# MotionGlove.net
KiCad netlist of a schematic drawn in Altium Designer
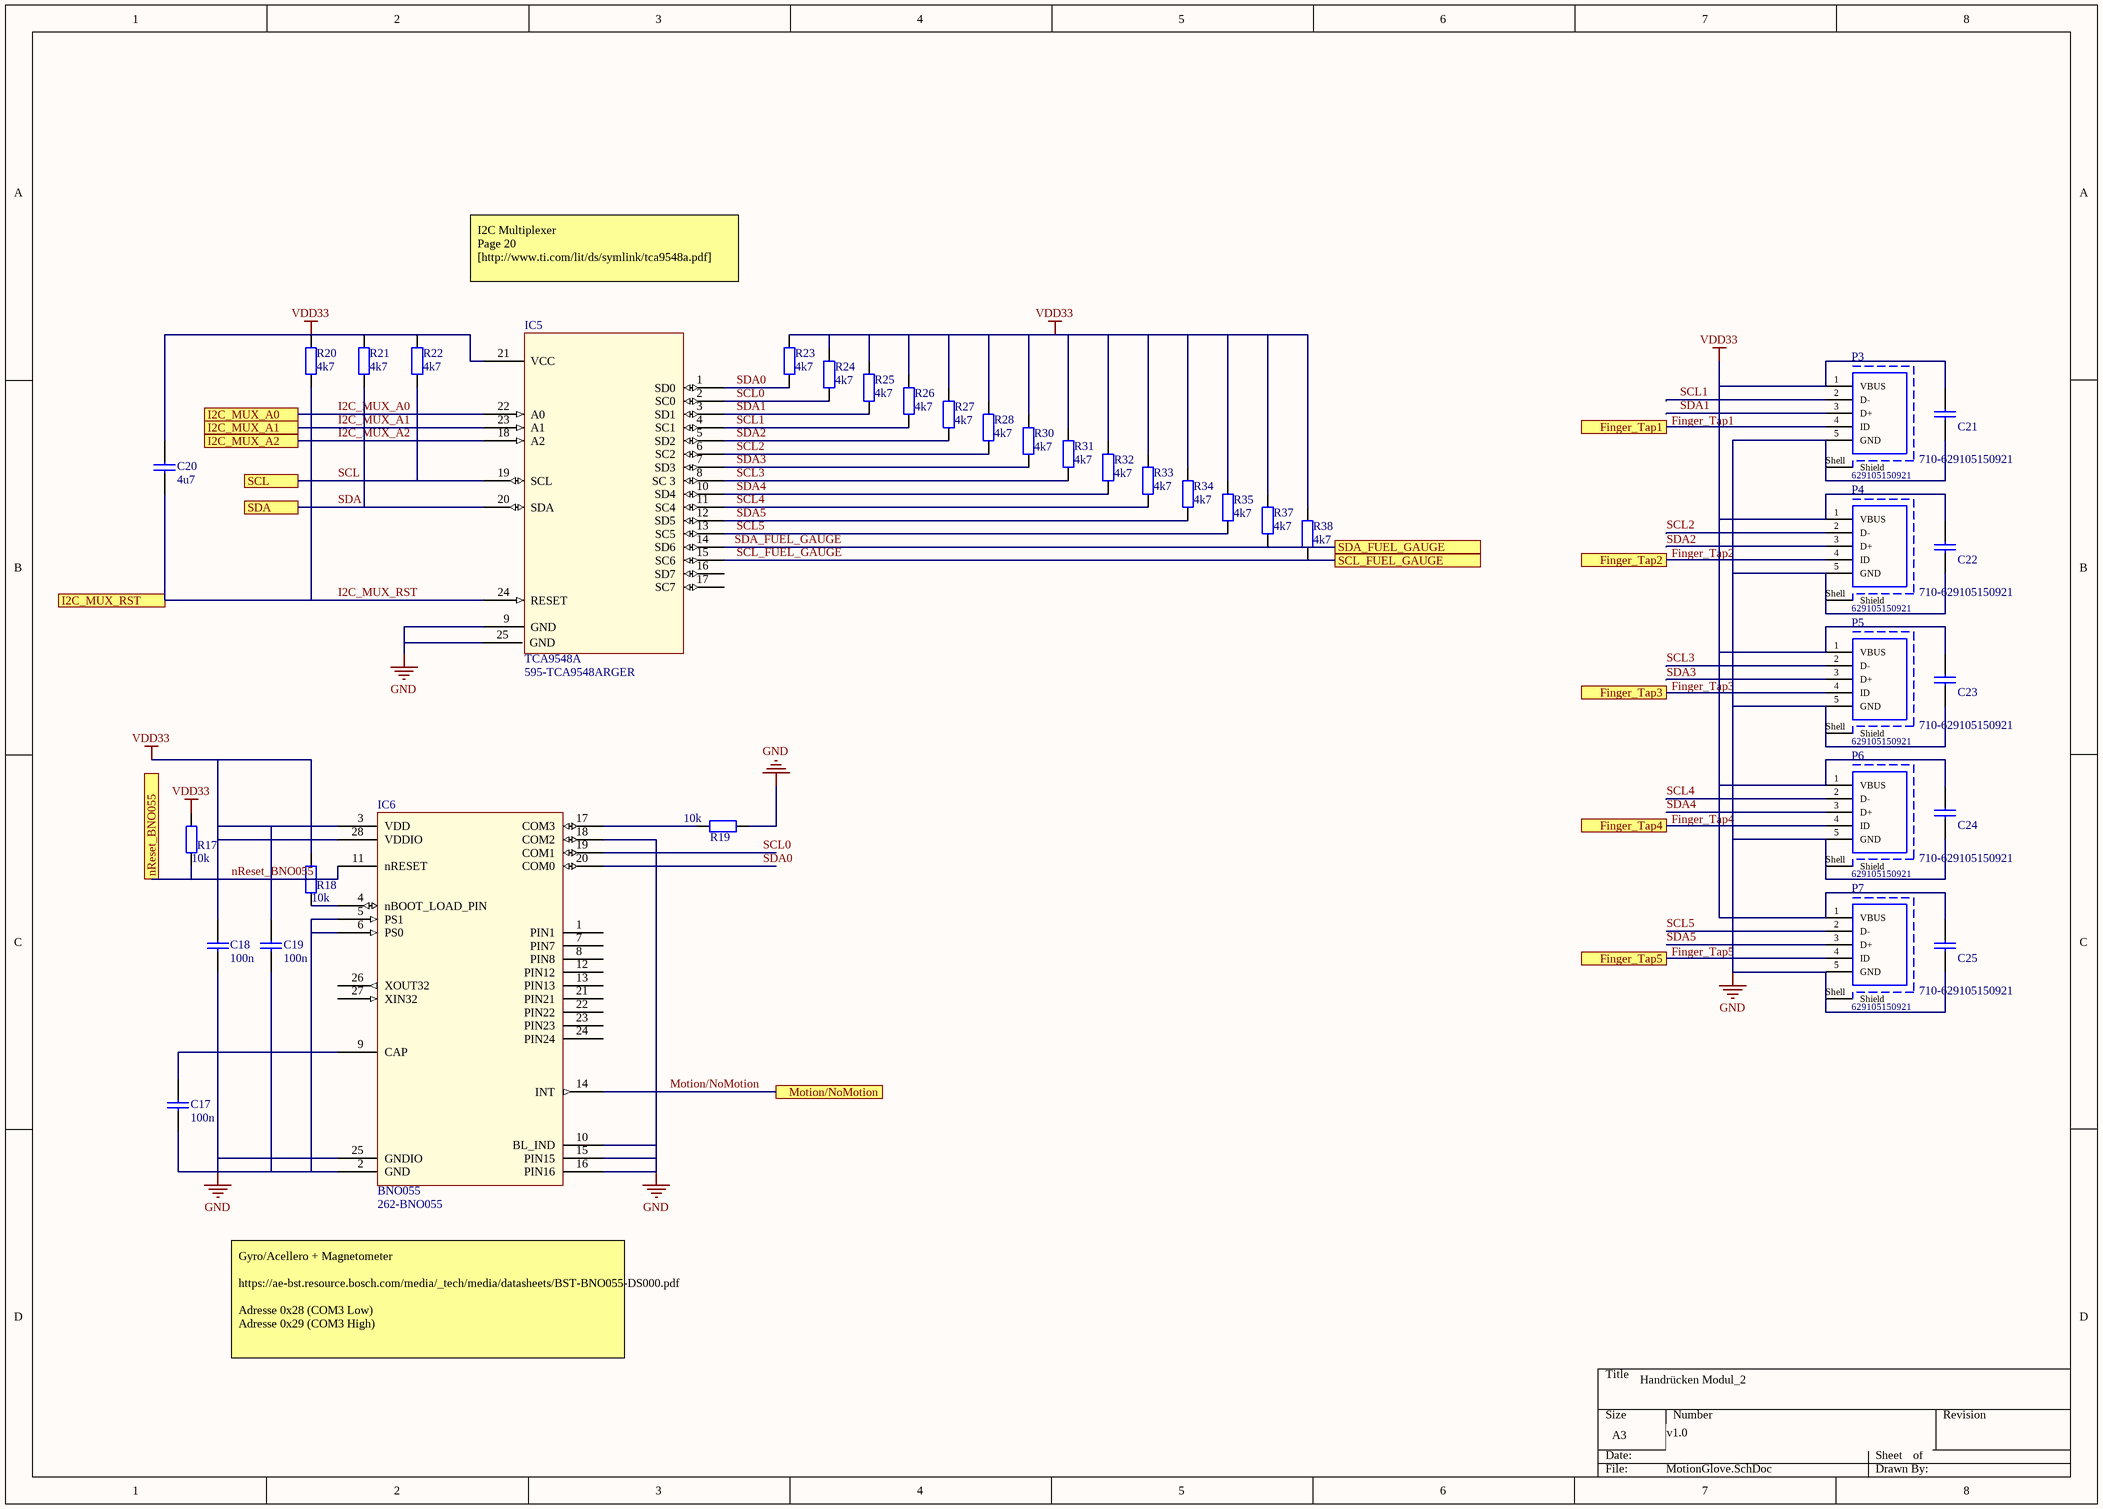
[diagram p0: MotionGlove.SchDoc]

(export (version "E")
  (design (tool "Eeschema 10.0.6"))
  (components
    (comp (ref "C17")
      (value "100n")
      (footprint "CAPC1005X55")
      (description "Ceramic Chip Capacitor")
      (fields (field (name "MANUFACTURER") "Kemet") (field (name "VOLTAGE") "16V"))
      (libsource (lib "SCT_MySQL_5.1") (part "Capacitor"))
    )
    (comp (ref "C18")
      (value "100n")
      (footprint "CAPC1005X55")
      (description "Ceramic Chip Capacitor")
      (fields (field (name "MANUFACTURER") "Kemet") (field (name "VOLTAGE") "16V"))
      (libsource (lib "SCT_MySQL_5.1") (part "Capacitor"))
    )
    (comp (ref "C19")
      (value "100n")
      (footprint "CAPC1005X55")
      (description "Ceramic Chip Capacitor")
      (fields (field (name "MANUFACTURER") "Kemet") (field (name "VOLTAGE") "16V"))
      (libsource (lib "SCT_MySQL_5.1") (part "Capacitor"))
    )
    (comp (ref "C20")
      (value "4u7")
      (footprint "CAPC1005X55")
      (description "Ceramic Chip Capacitor")
      (fields (field (name "MANUFACTURER") "Murata") (field (name "VOLTAGE") "6.3V"))
      (libsource (lib "SCT_MySQL_5.1") (part "Capacitor"))
    )
    (comp (ref "C21")
      (value "100n")
      (footprint "CAPC1005X55")
      (description "Ceramic Chip Capacitor")
      (fields (field (name "MANUFACTURER") "Kemet") (field (name "VOLTAGE") "16V"))
      (libsource (lib "SCT_MySQL_5.1") (part "Capacitor"))
    )
    (comp (ref "C22")
      (value "100n")
      (footprint "CAPC1005X55")
      (description "Ceramic Chip Capacitor")
      (fields (field (name "MANUFACTURER") "Kemet") (field (name "VOLTAGE") "16V"))
      (libsource (lib "SCT_MySQL_5.1") (part "Capacitor"))
    )
    (comp (ref "C23")
      (value "100n")
      (footprint "CAPC1005X55")
      (description "Ceramic Chip Capacitor")
      (fields (field (name "MANUFACTURER") "Kemet") (field (name "VOLTAGE") "16V"))
      (libsource (lib "SCT_MySQL_5.1") (part "Capacitor"))
    )
    (comp (ref "C24")
      (value "100n")
      (footprint "CAPC1005X55")
      (description "Ceramic Chip Capacitor")
      (fields (field (name "MANUFACTURER") "Kemet") (field (name "VOLTAGE") "16V"))
      (libsource (lib "SCT_MySQL_5.1") (part "Capacitor"))
    )
    (comp (ref "C25")
      (value "100n")
      (footprint "CAPC1005X55")
      (description "Ceramic Chip Capacitor")
      (fields (field (name "MANUFACTURER") "Kemet") (field (name "VOLTAGE") "16V"))
      (libsource (lib "SCT_MySQL_5.1") (part "Capacitor"))
    )
    (comp (ref "IC5")
      (value "TCA9548A")
      (footprint "TCA9548A-Q1")
      (fields (field (name "SUPPLIER PART NUMBER 1") "595-TCA9548ARGER"))
      (libsource (lib "Lib") (part "TCA9548A"))
    )
    (comp (ref "IC6")
      (value "BNO055")
      (footprint "BNO055")
      (fields (field (name "SUPPLIER PART NUMBER 1") "262-BNO055"))
      (libsource (lib "Lib") (part "BNO055"))
    )
    (comp (ref "P3")
      (value "629105150921")
      (footprint "629105150921")
      (description "Micro USB 2.0 Type AB Receptacle WR-COM, Horizontal, SMT")
      (fields
        (field (name "SUPPLIER PART NUMBER 1") "710-629105150921")
        (field (name "PUBLISHER") "Wurth Elektronik")
      )
      (libsource (lib "USB Connectors WR-USB") (part "629105150921"))
    )
    (comp (ref "P4")
      (value "629105150921")
      (footprint "629105150921")
      (description "Micro USB 2.0 Type AB Receptacle WR-COM, Horizontal, SMT")
      (fields
        (field (name "SUPPLIER PART NUMBER 1") "710-629105150921")
        (field (name "PUBLISHER") "Wurth Elektronik")
      )
      (libsource (lib "USB Connectors WR-USB") (part "629105150921"))
    )
    (comp (ref "P5")
      (value "629105150921")
      (footprint "629105150921")
      (description "Micro USB 2.0 Type AB Receptacle WR-COM, Horizontal, SMT")
      (fields
        (field (name "SUPPLIER PART NUMBER 1") "710-629105150921")
        (field (name "PUBLISHER") "Wurth Elektronik")
      )
      (libsource (lib "USB Connectors WR-USB") (part "629105150921"))
    )
    (comp (ref "P6")
      (value "629105150921")
      (footprint "629105150921")
      (description "Micro USB 2.0 Type AB Receptacle WR-COM, Horizontal, SMT")
      (fields
        (field (name "SUPPLIER PART NUMBER 1") "710-629105150921")
        (field (name "PUBLISHER") "Wurth Elektronik")
      )
      (libsource (lib "USB Connectors WR-USB") (part "629105150921"))
    )
    (comp (ref "P7")
      (value "629105150921")
      (footprint "629105150921")
      (description "Micro USB 2.0 Type AB Receptacle WR-COM, Horizontal, SMT")
      (fields
        (field (name "SUPPLIER PART NUMBER 1") "710-629105150921")
        (field (name "PUBLISHER") "Wurth Elektronik")
      )
      (libsource (lib "USB Connectors WR-USB") (part "629105150921"))
    )
    (comp (ref "R17")
      (value "10k")
      (footprint "RESC1005X40")
      (description "Resistor")
      (fields (field (name "MANUFACTURER") "Multicomp") (field (name "TOLERANCE") "±1%"))
      (libsource (lib "SCT_MySQL_5.1") (part "Resistor"))
    )
    (comp (ref "R18")
      (value "10k")
      (footprint "RESC1005X40")
      (description "Resistor")
      (fields (field (name "MANUFACTURER") "Multicomp") (field (name "TOLERANCE") "±1%"))
      (libsource (lib "SCT_MySQL_5.1") (part "Resistor"))
    )
    (comp (ref "R19")
      (value "10k")
      (footprint "RESC1005X40")
      (description "Resistor")
      (fields (field (name "MANUFACTURER") "Multicomp") (field (name "TOLERANCE") "±1%"))
      (libsource (lib "") (part "Resistor_1"))
    )
    (comp (ref "R20")
      (value "4k7")
      (footprint "RESC1005X40")
      (description "Resistor")
      (fields (field (name "MANUFACTURER") "Multicomp") (field (name "TOLERANCE") "±1%"))
      (libsource (lib "SCT_MySQL_5.1") (part "Resistor"))
    )
    (comp (ref "R21")
      (value "4k7")
      (footprint "RESC1005X40")
      (description "Resistor")
      (fields (field (name "MANUFACTURER") "Multicomp") (field (name "TOLERANCE") "±1%"))
      (libsource (lib "SCT_MySQL_5.1") (part "Resistor"))
    )
    (comp (ref "R22")
      (value "4k7")
      (footprint "RESC1005X40")
      (description "Resistor")
      (fields (field (name "MANUFACTURER") "Multicomp") (field (name "TOLERANCE") "±1%"))
      (libsource (lib "SCT_MySQL_5.1") (part "Resistor"))
    )
    (comp (ref "R23")
      (value "4k7")
      (footprint "RESC1005X40")
      (description "Resistor")
      (fields (field (name "MANUFACTURER") "Multicomp") (field (name "TOLERANCE") "±1%"))
      (libsource (lib "SCT_MySQL_5.1") (part "Resistor"))
    )
    (comp (ref "R24")
      (value "4k7")
      (footprint "RESC1005X40")
      (description "Resistor")
      (fields (field (name "MANUFACTURER") "Multicomp") (field (name "TOLERANCE") "±1%"))
      (libsource (lib "SCT_MySQL_5.1") (part "Resistor"))
    )
    (comp (ref "R25")
      (value "4k7")
      (footprint "RESC1005X40")
      (description "Resistor")
      (fields (field (name "MANUFACTURER") "Multicomp") (field (name "TOLERANCE") "±1%"))
      (libsource (lib "SCT_MySQL_5.1") (part "Resistor"))
    )
    (comp (ref "R26")
      (value "4k7")
      (footprint "RESC1005X40")
      (description "Resistor")
      (fields (field (name "MANUFACTURER") "Multicomp") (field (name "TOLERANCE") "±1%"))
      (libsource (lib "SCT_MySQL_5.1") (part "Resistor"))
    )
    (comp (ref "R27")
      (value "4k7")
      (footprint "RESC1005X40")
      (description "Resistor")
      (fields (field (name "MANUFACTURER") "Multicomp") (field (name "TOLERANCE") "±1%"))
      (libsource (lib "SCT_MySQL_5.1") (part "Resistor"))
    )
    (comp (ref "R28")
      (value "4k7")
      (footprint "RESC1005X40")
      (description "Resistor")
      (fields (field (name "MANUFACTURER") "Multicomp") (field (name "TOLERANCE") "±1%"))
      (libsource (lib "SCT_MySQL_5.1") (part "Resistor"))
    )
    (comp (ref "R30")
      (value "4k7")
      (footprint "RESC1005X40")
      (description "Resistor")
      (fields (field (name "MANUFACTURER") "Multicomp") (field (name "TOLERANCE") "±1%"))
      (libsource (lib "SCT_MySQL_5.1") (part "Resistor"))
    )
    (comp (ref "R31")
      (value "4k7")
      (footprint "RESC1005X40")
      (description "Resistor")
      (fields (field (name "MANUFACTURER") "Multicomp") (field (name "TOLERANCE") "±1%"))
      (libsource (lib "SCT_MySQL_5.1") (part "Resistor"))
    )
    (comp (ref "R32")
      (value "4k7")
      (footprint "RESC1005X40")
      (description "Resistor")
      (fields (field (name "MANUFACTURER") "Multicomp") (field (name "TOLERANCE") "±1%"))
      (libsource (lib "SCT_MySQL_5.1") (part "Resistor"))
    )
    (comp (ref "R33")
      (value "4k7")
      (footprint "RESC1005X40")
      (description "Resistor")
      (fields (field (name "MANUFACTURER") "Multicomp") (field (name "TOLERANCE") "±1%"))
      (libsource (lib "SCT_MySQL_5.1") (part "Resistor"))
    )
    (comp (ref "R34")
      (value "4k7")
      (footprint "RESC1005X40")
      (description "Resistor")
      (fields (field (name "MANUFACTURER") "Multicomp") (field (name "TOLERANCE") "±1%"))
      (libsource (lib "SCT_MySQL_5.1") (part "Resistor"))
    )
    (comp (ref "R35")
      (value "4k7")
      (footprint "RESC1005X40")
      (description "Resistor")
      (fields (field (name "MANUFACTURER") "Multicomp") (field (name "TOLERANCE") "±1%"))
      (libsource (lib "SCT_MySQL_5.1") (part "Resistor"))
    )
    (comp (ref "R37")
      (value "4k7")
      (footprint "RESC1005X40")
      (description "Resistor")
      (fields (field (name "MANUFACTURER") "Multicomp") (field (name "TOLERANCE") "±1%"))
      (libsource (lib "SCT_MySQL_5.1") (part "Resistor"))
    )
    (comp (ref "R38")
      (value "4k7")
      (footprint "RESC1005X40")
      (description "Resistor")
      (fields (field (name "MANUFACTURER") "Multicomp") (field (name "TOLERANCE") "±1%"))
      (libsource (lib "SCT_MySQL_5.1") (part "Resistor"))
    )
  )
  (nets
    (net (code "1") (name "/Finger_Tap1") (class "Default")
      (node (ref "P3") (pin "4") (pinfunction "ID_4") (pintype "passive"))
    )
    (net (code "2") (name "/Finger_Tap2") (class "Default")
      (node (ref "P4") (pin "4") (pinfunction "ID_4") (pintype "passive"))
    )
    (net (code "3") (name "/Finger_Tap3") (class "Default")
      (node (ref "P5") (pin "4") (pinfunction "ID_4") (pintype "passive"))
    )
    (net (code "4") (name "/Finger_Tap4") (class "Default")
      (node (ref "P6") (pin "4") (pinfunction "ID_4") (pintype "passive"))
    )
    (net (code "5") (name "/Finger_Tap5") (class "Default")
      (node (ref "P7") (pin "4") (pinfunction "ID_4") (pintype "passive"))
    )
    (net (code "6") (name "/I2C_MUX_A0") (class "Default")
      (node (ref "IC5") (pin "22") (pinfunction "A0_22") (pintype "input"))
    )
    (net (code "7") (name "/I2C_MUX_A1") (class "Default")
      (node (ref "IC5") (pin "23") (pinfunction "A1_23") (pintype "input"))
    )
    (net (code "8") (name "/I2C_MUX_A2") (class "Default")
      (node (ref "IC5") (pin "18") (pinfunction "A2_18") (pintype "input"))
    )
    (net (code "9") (name "/I2C_MUX_RST") (class "Default")
      (node (ref "C20") (pin "1") (pinfunction "1_1") (pintype "passive"))
      (node (ref "IC5") (pin "24") (pinfunction "RESET_24") (pintype "input"))
      (node (ref "R20") (pin "1") (pinfunction "1_1") (pintype "passive"))
    )
    (net (code "10") (name "/Motion{slash}NoMotion") (class "Default")
      (node (ref "IC6") (pin "14") (pinfunction "INT_14") (pintype "output"))
    )
    (net (code "11") (name "/SCL") (class "Default")
      (node (ref "IC5") (pin "19") (pinfunction "SCL_19") (pintype "bidirectional"))
      (node (ref "R22") (pin "1") (pinfunction "1_1") (pintype "passive"))
    )
    (net (code "12") (name "/SCL0") (class "Default")
      (node (ref "IC5") (pin "2") (pinfunction "SC0_2") (pintype "bidirectional"))
      (node (ref "IC6") (pin "19") (pinfunction "COM1_19") (pintype "bidirectional"))
      (node (ref "R24") (pin "1") (pinfunction "1_1") (pintype "passive"))
    )
    (net (code "13") (name "/SCL1") (class "Default")
      (node (ref "IC5") (pin "4") (pinfunction "SC1_4") (pintype "bidirectional"))
      (node (ref "P3") (pin "2") (pinfunction "D-_2") (pintype "passive"))
      (node (ref "R26") (pin "1") (pinfunction "1_1") (pintype "passive"))
    )
    (net (code "14") (name "/SCL2") (class "Default")
      (node (ref "IC5") (pin "6") (pinfunction "SC2_6") (pintype "bidirectional"))
      (node (ref "P4") (pin "2") (pinfunction "D-_2") (pintype "passive"))
      (node (ref "R28") (pin "1") (pinfunction "1_1") (pintype "passive"))
    )
    (net (code "15") (name "/SCL3") (class "Default")
      (node (ref "IC5") (pin "8") (pinfunction "SC_3_8") (pintype "bidirectional"))
      (node (ref "P5") (pin "2") (pinfunction "D-_2") (pintype "passive"))
      (node (ref "R31") (pin "1") (pinfunction "1_1") (pintype "passive"))
    )
    (net (code "16") (name "/SCL4") (class "Default")
      (node (ref "IC5") (pin "11") (pinfunction "SC4_11") (pintype "bidirectional"))
      (node (ref "P6") (pin "2") (pinfunction "D-_2") (pintype "passive"))
      (node (ref "R33") (pin "1") (pinfunction "1_1") (pintype "passive"))
    )
    (net (code "17") (name "/SCL5") (class "Default")
      (node (ref "IC5") (pin "13") (pinfunction "SC5_13") (pintype "bidirectional"))
      (node (ref "P7") (pin "2") (pinfunction "D-_2") (pintype "passive"))
      (node (ref "R35") (pin "1") (pinfunction "1_1") (pintype "passive"))
    )
    (net (code "18") (name "/SCL_FUEL_GAUGE") (class "Default")
      (node (ref "IC5") (pin "15") (pinfunction "SC6_15") (pintype "bidirectional"))
      (node (ref "R38") (pin "1") (pinfunction "1_1") (pintype "passive"))
    )
    (net (code "19") (name "/SDA") (class "Default")
      (node (ref "IC5") (pin "20") (pinfunction "SDA_20") (pintype "bidirectional"))
      (node (ref "R21") (pin "1") (pinfunction "1_1") (pintype "passive"))
    )
    (net (code "20") (name "/SDA0") (class "Default")
      (node (ref "IC5") (pin "1") (pinfunction "SD0_1") (pintype "bidirectional"))
      (node (ref "IC6") (pin "20") (pinfunction "COM0_20") (pintype "bidirectional"))
      (node (ref "R23") (pin "1") (pinfunction "1_1") (pintype "passive"))
    )
    (net (code "21") (name "/SDA1") (class "Default")
      (node (ref "IC5") (pin "3") (pinfunction "SD1_3") (pintype "bidirectional"))
      (node (ref "P3") (pin "3") (pinfunction "D+_3") (pintype "passive"))
      (node (ref "R25") (pin "1") (pinfunction "1_1") (pintype "passive"))
    )
    (net (code "22") (name "/SDA2") (class "Default")
      (node (ref "IC5") (pin "5") (pinfunction "SD2_5") (pintype "bidirectional"))
      (node (ref "P4") (pin "3") (pinfunction "D+_3") (pintype "passive"))
      (node (ref "R27") (pin "1") (pinfunction "1_1") (pintype "passive"))
    )
    (net (code "23") (name "/SDA3") (class "Default")
      (node (ref "IC5") (pin "7") (pinfunction "SD3_7") (pintype "bidirectional"))
      (node (ref "P5") (pin "3") (pinfunction "D+_3") (pintype "passive"))
      (node (ref "R30") (pin "1") (pinfunction "1_1") (pintype "passive"))
    )
    (net (code "24") (name "/SDA4") (class "Default")
      (node (ref "IC5") (pin "10") (pinfunction "SD4_10") (pintype "bidirectional"))
      (node (ref "P6") (pin "3") (pinfunction "D+_3") (pintype "passive"))
      (node (ref "R32") (pin "1") (pinfunction "1_1") (pintype "passive"))
    )
    (net (code "25") (name "/SDA5") (class "Default")
      (node (ref "IC5") (pin "12") (pinfunction "SD5_12") (pintype "bidirectional"))
      (node (ref "P7") (pin "3") (pinfunction "D+_3") (pintype "passive"))
      (node (ref "R34") (pin "1") (pinfunction "1_1") (pintype "passive"))
    )
    (net (code "26") (name "/SDA_FUEL_GAUGE") (class "Default")
      (node (ref "IC5") (pin "14") (pinfunction "SD6_14") (pintype "bidirectional"))
      (node (ref "R37") (pin "1") (pinfunction "1_1") (pintype "passive"))
    )
    (net (code "27") (name "/nReset_BNO055") (class "Default")
      (node (ref "IC6") (pin "11") (pinfunction "nRESET_11") (pintype "passive"))
      (node (ref "R17") (pin "1") (pinfunction "1_1") (pintype "passive"))
    )
    (net (code "28") (name "GND") (class "Default")
      (node (ref "C17") (pin "1") (pinfunction "1_1") (pintype "passive"))
      (node (ref "C18") (pin "1") (pinfunction "1_1") (pintype "passive"))
      (node (ref "C19") (pin "1") (pinfunction "1_1") (pintype "passive"))
      (node (ref "C21") (pin "1") (pinfunction "1_1") (pintype "passive"))
      (node (ref "C22") (pin "1") (pinfunction "1_1") (pintype "passive"))
      (node (ref "C23") (pin "1") (pinfunction "1_1") (pintype "passive"))
      (node (ref "C24") (pin "1") (pinfunction "1_1") (pintype "passive"))
      (node (ref "C25") (pin "1") (pinfunction "1_1") (pintype "passive"))
      (node (ref "IC5") (pin "25") (pinfunction "GND_25") (pintype "passive"))
      (node (ref "IC5") (pin "9") (pinfunction "GND_9") (pintype "power_in"))
      (node (ref "IC6") (pin "10") (pinfunction "BL_IND_10") (pintype "passive"))
      (node (ref "IC6") (pin "15") (pinfunction "PIN15_15") (pintype "power_in"))
      (node (ref "IC6") (pin "16") (pinfunction "PIN16_16") (pintype "power_in"))
      (node (ref "IC6") (pin "18") (pinfunction "COM2_18") (pintype "bidirectional"))
      (node (ref "IC6") (pin "2") (pinfunction "GND_2") (pintype "power_in"))
      (node (ref "IC6") (pin "25") (pinfunction "GNDIO_25") (pintype "power_in"))
      (node (ref "IC6") (pin "5") (pinfunction "PS1_5") (pintype "input"))
      (node (ref "IC6") (pin "6") (pinfunction "PS0_6") (pintype "input"))
      (node (ref "P3") (pin "5") (pinfunction "GND_5") (pintype "passive"))
      (node (ref "P3") (pin "Shell") (pinfunction "Shield_Shell") (pintype "passive"))
      (node (ref "P4") (pin "5") (pinfunction "GND_5") (pintype "passive"))
      (node (ref "P4") (pin "Shell") (pinfunction "Shield_Shell") (pintype "passive"))
      (node (ref "P5") (pin "5") (pinfunction "GND_5") (pintype "passive"))
      (node (ref "P5") (pin "Shell") (pinfunction "Shield_Shell") (pintype "passive"))
      (node (ref "P6") (pin "5") (pinfunction "GND_5") (pintype "passive"))
      (node (ref "P6") (pin "Shell") (pinfunction "Shield_Shell") (pintype "passive"))
      (node (ref "P7") (pin "5") (pinfunction "GND_5") (pintype "passive"))
      (node (ref "P7") (pin "Shell") (pinfunction "Shield_Shell") (pintype "passive"))
      (node (ref "R19") (pin "2") (pinfunction "2_2") (pintype "passive"))
    )
    (net (code "29") (name "Net-(IC6-CAP)") (class "Default")
      (node (ref "C17") (pin "2") (pinfunction "2_2") (pintype "passive"))
      (node (ref "IC6") (pin "9") (pinfunction "CAP_9") (pintype "passive"))
    )
    (net (code "30") (name "Net-(IC6-COM3)") (class "Default")
      (node (ref "IC6") (pin "17") (pinfunction "COM3_17") (pintype "bidirectional"))
      (node (ref "R19") (pin "1") (pinfunction "1_1") (pintype "passive"))
    )
    (net (code "31") (name "Net-(IC6-nBOOT_LOAD_PIN)") (class "Default")
      (node (ref "IC6") (pin "4") (pinfunction "nBOOT_LOAD_PIN_4") (pintype "bidirectional"))
      (node (ref "R18") (pin "1") (pinfunction "1_1") (pintype "passive"))
    )
    (net (code "32") (name "VDD33") (class "Default")
      (node (ref "C18") (pin "2") (pinfunction "2_2") (pintype "passive"))
      (node (ref "C19") (pin "2") (pinfunction "2_2") (pintype "passive"))
      (node (ref "C20") (pin "2") (pinfunction "2_2") (pintype "passive"))
      (node (ref "C21") (pin "2") (pinfunction "2_2") (pintype "passive"))
      (node (ref "C22") (pin "2") (pinfunction "2_2") (pintype "passive"))
      (node (ref "C23") (pin "2") (pinfunction "2_2") (pintype "passive"))
      (node (ref "C24") (pin "2") (pinfunction "2_2") (pintype "passive"))
      (node (ref "C25") (pin "2") (pinfunction "2_2") (pintype "passive"))
      (node (ref "IC5") (pin "21") (pinfunction "VCC_21") (pintype "power_in"))
      (node (ref "IC6") (pin "28") (pinfunction "VDDIO_28") (pintype "power_in"))
      (node (ref "IC6") (pin "3") (pinfunction "VDD_3") (pintype "power_in"))
      (node (ref "P3") (pin "1") (pinfunction "VBUS_1") (pintype "passive"))
      (node (ref "P4") (pin "1") (pinfunction "VBUS_1") (pintype "passive"))
      (node (ref "P5") (pin "1") (pinfunction "VBUS_1") (pintype "passive"))
      (node (ref "P6") (pin "1") (pinfunction "VBUS_1") (pintype "passive"))
      (node (ref "P7") (pin "1") (pinfunction "VBUS_1") (pintype "passive"))
      (node (ref "R17") (pin "2") (pinfunction "2_2") (pintype "passive"))
      (node (ref "R18") (pin "2") (pinfunction "2_2") (pintype "passive"))
      (node (ref "R20") (pin "2") (pinfunction "2_2") (pintype "passive"))
      (node (ref "R21") (pin "2") (pinfunction "2_2") (pintype "passive"))
      (node (ref "R22") (pin "2") (pinfunction "2_2") (pintype "passive"))
      (node (ref "R23") (pin "2") (pinfunction "2_2") (pintype "passive"))
      (node (ref "R24") (pin "2") (pinfunction "2_2") (pintype "passive"))
      (node (ref "R25") (pin "2") (pinfunction "2_2") (pintype "passive"))
      (node (ref "R26") (pin "2") (pinfunction "2_2") (pintype "passive"))
      (node (ref "R27") (pin "2") (pinfunction "2_2") (pintype "passive"))
      (node (ref "R28") (pin "2") (pinfunction "2_2") (pintype "passive"))
      (node (ref "R30") (pin "2") (pinfunction "2_2") (pintype "passive"))
      (node (ref "R31") (pin "2") (pinfunction "2_2") (pintype "passive"))
      (node (ref "R32") (pin "2") (pinfunction "2_2") (pintype "passive"))
      (node (ref "R33") (pin "2") (pinfunction "2_2") (pintype "passive"))
      (node (ref "R34") (pin "2") (pinfunction "2_2") (pintype "passive"))
      (node (ref "R35") (pin "2") (pinfunction "2_2") (pintype "passive"))
      (node (ref "R37") (pin "2") (pinfunction "2_2") (pintype "passive"))
      (node (ref "R38") (pin "2") (pinfunction "2_2") (pintype "passive"))
    )
    (net (code "33") (name "unconnected-(IC5-SC7-Pad17)") (class "Default")
      (node (ref "IC5") (pin "17") (pinfunction "SC7_17") (pintype "bidirectional"))
    )
    (net (code "34") (name "unconnected-(IC5-SD7-Pad16)") (class "Default")
      (node (ref "IC5") (pin "16") (pinfunction "SD7_16") (pintype "bidirectional"))
    )
    (net (code "35") (name "unconnected-(IC6-PIN1-Pad1)") (class "Default")
      (node (ref "IC6") (pin "1") (pinfunction "PIN1_1") (pintype "passive"))
    )
    (net (code "36") (name "unconnected-(IC6-PIN7-Pad7)") (class "Default")
      (node (ref "IC6") (pin "7") (pinfunction "PIN7_7") (pintype "passive"))
    )
    (net (code "37") (name "unconnected-(IC6-PIN8-Pad8)") (class "Default")
      (node (ref "IC6") (pin "8") (pinfunction "PIN8_8") (pintype "passive"))
    )
    (net (code "38") (name "unconnected-(IC6-PIN12-Pad12)") (class "Default")
      (node (ref "IC6") (pin "12") (pinfunction "PIN12_12") (pintype "passive"))
    )
    (net (code "39") (name "unconnected-(IC6-PIN13-Pad13)") (class "Default")
      (node (ref "IC6") (pin "13") (pinfunction "PIN13_13") (pintype "passive"))
    )
    (net (code "40") (name "unconnected-(IC6-PIN21-Pad21)") (class "Default")
      (node (ref "IC6") (pin "21") (pinfunction "PIN21_21") (pintype "passive"))
    )
    (net (code "41") (name "unconnected-(IC6-PIN22-Pad22)") (class "Default")
      (node (ref "IC6") (pin "22") (pinfunction "PIN22_22") (pintype "passive"))
    )
    (net (code "42") (name "unconnected-(IC6-PIN23-Pad23)") (class "Default")
      (node (ref "IC6") (pin "23") (pinfunction "PIN23_23") (pintype "passive"))
    )
    (net (code "43") (name "unconnected-(IC6-PIN24-Pad24)") (class "Default")
      (node (ref "IC6") (pin "24") (pinfunction "PIN24_24") (pintype "passive"))
    )
    (net (code "44") (name "unconnected-(IC6-XIN32-Pad27)") (class "Default")
      (node (ref "IC6") (pin "27") (pinfunction "XIN32_27") (pintype "input"))
    )
    (net (code "45") (name "unconnected-(IC6-XOUT32-Pad26)") (class "Default")
      (node (ref "IC6") (pin "26") (pinfunction "XOUT32_26") (pintype "output"))
    )
  )
)
